# MSXII_Controller_Breakout.net
KiCad netlist of a schematic drawn in Altium Designer
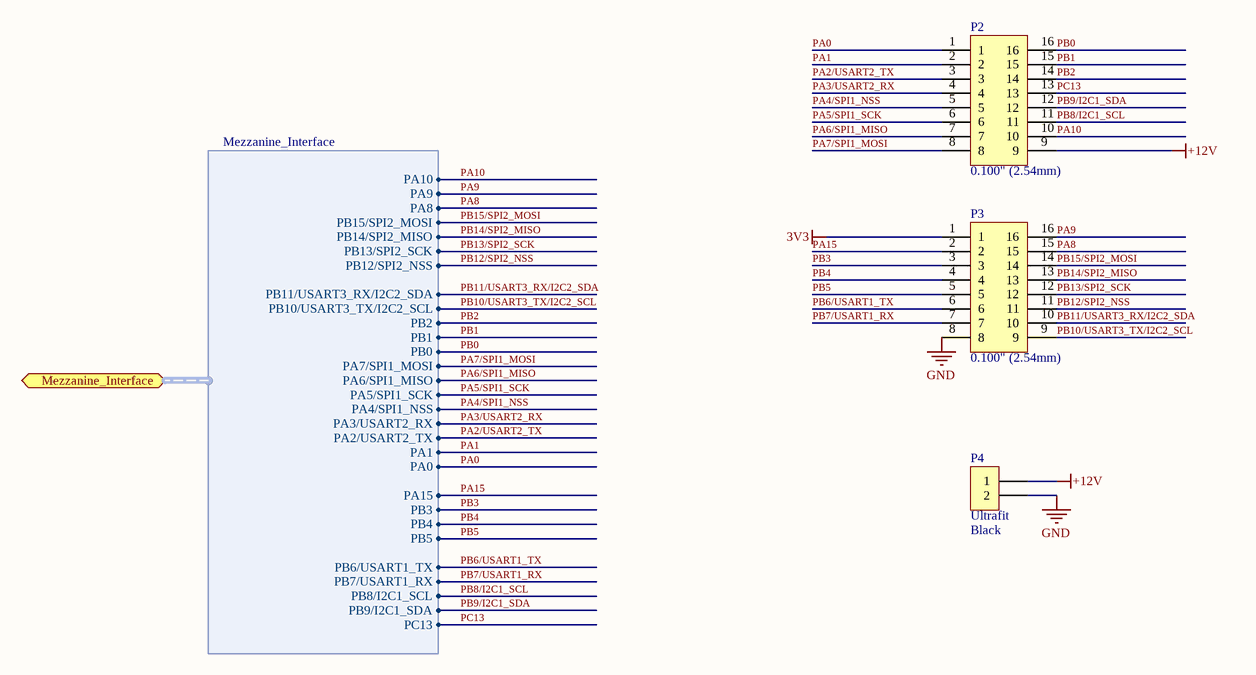
[diagram p0: MSXII_Controller_Breakout.SchDoc]

(export (version "E")
  (design (tool "Eeschema 10.0.6"))
  (components
    (comp (ref "P2")
      (value "16POS")
      (footprint "CONN, 16POS 0.100\" Header")
      (description "CONN HEADER .100\" DUAL STR 16POS")
      (fields (field (name "PITCH - MATING") "0.100\" (2.54mm)"))
      (libsource (lib "Schematic Diagrams") (part "CONN 16POS HEADR MALE 0.1{dblquote}"))
    )
    (comp (ref "P3")
      (value "16POS")
      (footprint "CONN, 16POS 0.100\" Header")
      (description "CONN HEADER .100\" DUAL STR 16POS")
      (fields (field (name "PITCH - MATING") "0.100\" (2.54mm)"))
      (libsource (lib "Schematic Diagrams") (part "CONN 16POS HEADR MALE 0.1{dblquote}"))
    )
    (comp (ref "P4")
      (value "CONN 2POS ULTRA-FIT 0.138\"")
      (footprint "CONN, 2POS ULTRA-FIT")
      (description "2 Positions Header, Shrouded Connector 0.138\" (3.50mm) Through Hole Gold")
      (fields
        (field (name "MANUFACTURER") "Molex, LLC")
        (field (name "MANUFACTURER PART NUMBER") "1722871102")
        (field (name "INSULATION COLOR") "Black")
        (field (name "SERIES") "Ultrafit")
      )
      (libsource (lib "Schematic Diagrams") (part "CONN 2POS ULTRA-FIT 0.138{dblquote}"))
    )
  )
  (nets
    (net (code "2") (name "+12V") (class "Default")
      (node (ref "P2") (pin "9") (pinfunction "9_9") (pintype "passive"))
      (node (ref "P4") (pin "1") (pinfunction "1_1") (pintype "passive"))
    )
    (net (code "3") (name "/PA0") (class "Default")
      (node (ref "P2") (pin "1") (pinfunction "1_1") (pintype "passive"))
    )
    (net (code "4") (name "/PA1") (class "Default")
      (node (ref "P2") (pin "2") (pinfunction "2_2") (pintype "passive"))
    )
    (net (code "5") (name "/PA2{slash}USART2_TX") (class "Default")
      (node (ref "P2") (pin "3") (pinfunction "3_3") (pintype "passive"))
    )
    (net (code "6") (name "/PA3{slash}USART2_RX") (class "Default")
      (node (ref "P2") (pin "4") (pinfunction "4_4") (pintype "passive"))
    )
    (net (code "7") (name "/PA4{slash}SPI1_NSS") (class "Default")
      (node (ref "P2") (pin "5") (pinfunction "5_5") (pintype "passive"))
    )
    (net (code "8") (name "/PA5{slash}SPI1_SCK") (class "Default")
      (node (ref "P2") (pin "6") (pinfunction "6_6") (pintype "passive"))
    )
    (net (code "9") (name "/PA6{slash}SPI1_MISO") (class "Default")
      (node (ref "P2") (pin "7") (pinfunction "7_7") (pintype "passive"))
    )
    (net (code "10") (name "/PA7{slash}SPI1_MOSI") (class "Default")
      (node (ref "P2") (pin "8") (pinfunction "8_8") (pintype "passive"))
    )
    (net (code "11") (name "/PA8") (class "Default")
      (node (ref "P3") (pin "15") (pinfunction "15_15") (pintype "passive"))
    )
    (net (code "12") (name "/PA9") (class "Default")
      (node (ref "P3") (pin "16") (pinfunction "16_16") (pintype "passive"))
    )
    (net (code "13") (name "/PA10") (class "Default")
      (node (ref "P2") (pin "10") (pinfunction "10_10") (pintype "passive"))
    )
    (net (code "14") (name "/PA15") (class "Default")
      (node (ref "P3") (pin "2") (pinfunction "2_2") (pintype "passive"))
    )
    (net (code "15") (name "/PB0") (class "Default")
      (node (ref "P2") (pin "16") (pinfunction "16_16") (pintype "passive"))
    )
    (net (code "16") (name "/PB1") (class "Default")
      (node (ref "P2") (pin "15") (pinfunction "15_15") (pintype "passive"))
    )
    (net (code "17") (name "/PB2") (class "Default")
      (node (ref "P2") (pin "14") (pinfunction "14_14") (pintype "passive"))
    )
    (net (code "18") (name "/PB3") (class "Default")
      (node (ref "P3") (pin "3") (pinfunction "3_3") (pintype "passive"))
    )
    (net (code "19") (name "/PB4") (class "Default")
      (node (ref "P3") (pin "4") (pinfunction "4_4") (pintype "passive"))
    )
    (net (code "20") (name "/PB5") (class "Default")
      (node (ref "P3") (pin "5") (pinfunction "5_5") (pintype "passive"))
    )
    (net (code "21") (name "/PB6{slash}USART1_TX") (class "Default")
      (node (ref "P3") (pin "6") (pinfunction "6_6") (pintype "passive"))
    )
    (net (code "22") (name "/PB7{slash}USART1_RX") (class "Default")
      (node (ref "P3") (pin "7") (pinfunction "7_7") (pintype "passive"))
    )
    (net (code "23") (name "/PB8{slash}I2C1_SCL") (class "Default")
      (node (ref "P2") (pin "11") (pinfunction "11_11") (pintype "passive"))
    )
    (net (code "24") (name "/PB9{slash}I2C1_SDA") (class "Default")
      (node (ref "P2") (pin "12") (pinfunction "12_12") (pintype "passive"))
    )
    (net (code "25") (name "/PB10{slash}USART3_TX{slash}I2C2_SCL") (class "Default")
      (node (ref "P3") (pin "9") (pinfunction "9_9") (pintype "passive"))
    )
    (net (code "26") (name "/PB11{slash}USART3_RX{slash}I2C2_SDA") (class "Default")
      (node (ref "P3") (pin "10") (pinfunction "10_10") (pintype "passive"))
    )
    (net (code "27") (name "/PB12{slash}SPI2_NSS") (class "Default")
      (node (ref "P3") (pin "11") (pinfunction "11_11") (pintype "passive"))
    )
    (net (code "28") (name "/PB13{slash}SPI2_SCK") (class "Default")
      (node (ref "P3") (pin "12") (pinfunction "12_12") (pintype "passive"))
    )
    (net (code "29") (name "/PB14{slash}SPI2_MISO") (class "Default")
      (node (ref "P3") (pin "13") (pinfunction "13_13") (pintype "passive"))
    )
    (net (code "30") (name "/PB15{slash}SPI2_MOSI") (class "Default")
      (node (ref "P3") (pin "14") (pinfunction "14_14") (pintype "passive"))
    )
    (net (code "31") (name "/PC13") (class "Default")
      (node (ref "P2") (pin "13") (pinfunction "13_13") (pintype "passive"))
    )
    (net (code "33") (name "3V3") (class "Default")
      (node (ref "P3") (pin "1") (pinfunction "1_1") (pintype "passive"))
    )
    (net (code "34") (name "GND") (class "Default")
      (node (ref "P3") (pin "8") (pinfunction "8_8") (pintype "passive"))
      (node (ref "P4") (pin "2") (pinfunction "2_2") (pintype "passive"))
    )
  )
)
